# controller.net
KiCad netlist of a schematic drawn in EAGLE
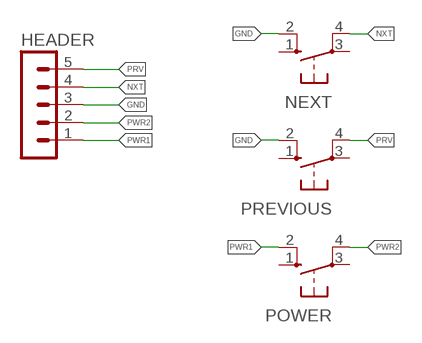
[diagram p0: schematic, sheet 1]

(export (version "E")
  (design (tool "Eeschema 10.0.6"))
  (components
    (comp (ref "HEADER")
      (value "MA05-1")
      (footprint "eagle-import:MA05-1")
      (libsource (lib "eagle-import") (part "MA05-1"))
    )
    (comp (ref "NEXT")
      (value "10-XX")
      (footprint "eagle-import:B3F-10XX")
      (fields (field (name "MPN") "B3F-1000"))
      (libsource (lib "eagle-import") (part "10-XX"))
    )
    (comp (ref "POWER")
      (value "10-XX")
      (footprint "eagle-import:B3F-10XX")
      (fields (field (name "MPN") "B3F-1000"))
      (libsource (lib "eagle-import") (part "10-XX"))
    )
    (comp (ref "PREVIOUS")
      (value "10-XX")
      (footprint "eagle-import:B3F-10XX")
      (fields (field (name "MPN") "B3F-1000"))
      (libsource (lib "eagle-import") (part "10-XX"))
    )
  )
  (nets
    (net (code "1") (name "GND") (class "Default")
      (node (ref "HEADER") (pin "3") (pinfunction "3_3") (pintype "passive"))
      (node (ref "NEXT") (pin "2") (pinfunction "S1_2") (pintype "passive"))
      (node (ref "PREVIOUS") (pin "2") (pinfunction "S1_2") (pintype "passive"))
    )
    (net (code "2") (name "NXT") (class "Default")
      (node (ref "HEADER") (pin "4") (pinfunction "4_4") (pintype "passive"))
      (node (ref "NEXT") (pin "4") (pinfunction "P1_4") (pintype "passive"))
    )
    (net (code "3") (name "PRV") (class "Default")
      (node (ref "HEADER") (pin "5") (pinfunction "5_5") (pintype "passive"))
      (node (ref "PREVIOUS") (pin "4") (pinfunction "P1_4") (pintype "passive"))
    )
    (net (code "4") (name "PWR1") (class "Default")
      (node (ref "HEADER") (pin "1") (pinfunction "1_1") (pintype "passive"))
      (node (ref "POWER") (pin "2") (pinfunction "S1_2") (pintype "passive"))
    )
    (net (code "5") (name "PWR2") (class "Default")
      (node (ref "HEADER") (pin "2") (pinfunction "2_2") (pintype "passive"))
      (node (ref "POWER") (pin "4") (pinfunction "P1_4") (pintype "passive"))
    )
    (net (code "6") (name "unconnected-(NEXT-P-Pad3)") (class "Default")
      (node (ref "NEXT") (pin "3") (pinfunction "P_3") (pintype "passive"))
    )
    (net (code "7") (name "unconnected-(NEXT-S-Pad1)") (class "Default")
      (node (ref "NEXT") (pin "1") (pinfunction "S_1") (pintype "passive"))
    )
    (net (code "8") (name "unconnected-(POWER-P-Pad3)") (class "Default")
      (node (ref "POWER") (pin "3") (pinfunction "P_3") (pintype "passive"))
    )
    (net (code "9") (name "unconnected-(POWER-S-Pad1)") (class "Default")
      (node (ref "POWER") (pin "1") (pinfunction "S_1") (pintype "passive"))
    )
    (net (code "10") (name "unconnected-(PREVIOUS-P-Pad3)") (class "Default")
      (node (ref "PREVIOUS") (pin "3") (pinfunction "P_3") (pintype "passive"))
    )
    (net (code "11") (name "unconnected-(PREVIOUS-S-Pad1)") (class "Default")
      (node (ref "PREVIOUS") (pin "1") (pinfunction "S_1") (pintype "passive"))
    )
  )
)
